# MagMemsAmpli_V6.net
KiCad netlist of a schematic drawn in EAGLE
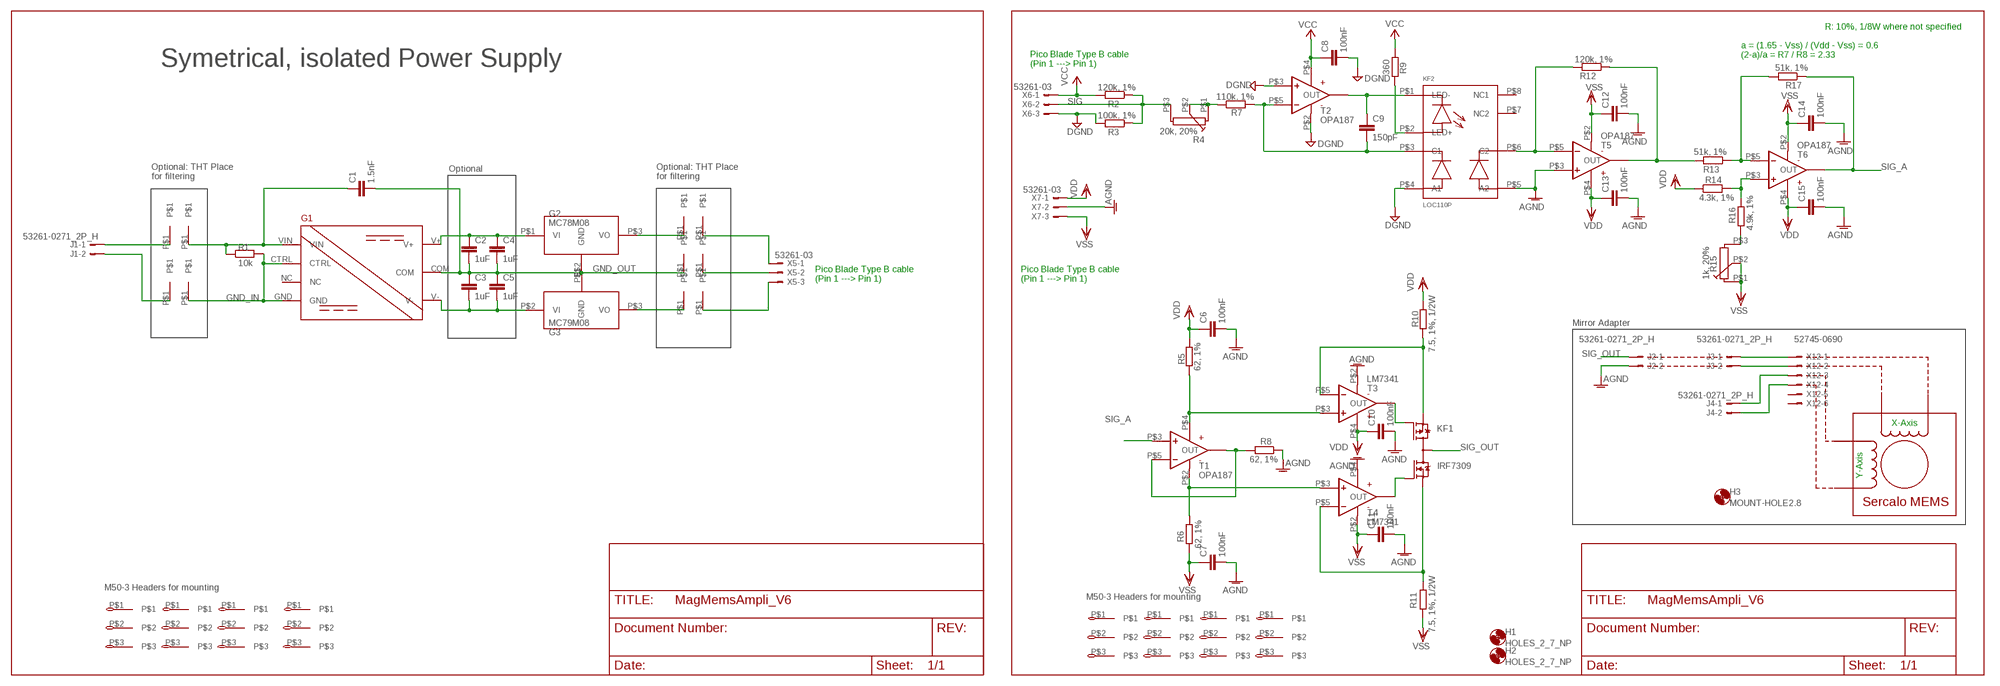
[diagram p0: schematic, sheet 1]

(export (version "E")
  (design (tool "Eeschema 10.0.6"))
  (components
    (comp (ref "C1")
      (value "1.5nF")
      (footprint "eagle-import:C0805K")
      (libsource (lib "eagle-import") (part "C-EUC0805K"))
    )
    (comp (ref "C2")
      (value "1uF")
      (footprint "eagle-import:C0805K")
      (libsource (lib "eagle-import") (part "C-EUC0805K"))
    )
    (comp (ref "C3")
      (value "1uF")
      (footprint "eagle-import:C0805K")
      (libsource (lib "eagle-import") (part "C-EUC0805K"))
    )
    (comp (ref "C4")
      (value "1uF")
      (footprint "eagle-import:C0805K")
      (libsource (lib "eagle-import") (part "C-EUC0805K"))
    )
    (comp (ref "C5")
      (value "1uF")
      (footprint "eagle-import:C0805K")
      (libsource (lib "eagle-import") (part "C-EUC0805K"))
    )
    (comp (ref "C6")
      (value "100nF")
      (footprint "eagle-import:C0603K")
      (libsource (lib "eagle-import") (part "C-EUC0603K"))
    )
    (comp (ref "C7")
      (value "100nF")
      (footprint "eagle-import:C0603K")
      (libsource (lib "eagle-import") (part "C-EUC0603K"))
    )
    (comp (ref "C8")
      (value "100nF")
      (footprint "eagle-import:C0603K")
      (libsource (lib "eagle-import") (part "C-EUC0603K"))
    )
    (comp (ref "C9")
      (value "150pF")
      (footprint "eagle-import:C0603K")
      (libsource (lib "eagle-import") (part "C-EUC0603K"))
    )
    (comp (ref "C10")
      (value "100nF")
      (footprint "eagle-import:C0603K")
      (libsource (lib "eagle-import") (part "C-EUC0603K"))
    )
    (comp (ref "C11")
      (value "100nF")
      (footprint "eagle-import:C0603K")
      (libsource (lib "eagle-import") (part "C-EUC0603K"))
    )
    (comp (ref "C12")
      (value "100nF")
      (footprint "eagle-import:C0603K")
      (libsource (lib "eagle-import") (part "C-EUC0603K"))
    )
    (comp (ref "C13")
      (value "100nF")
      (footprint "eagle-import:C0603K")
      (libsource (lib "eagle-import") (part "C-EUC0603K"))
    )
    (comp (ref "C14")
      (value "100nF")
      (footprint "eagle-import:C0603K")
      (libsource (lib "eagle-import") (part "C-EUC0603K"))
    )
    (comp (ref "C15")
      (value "100nF")
      (footprint "eagle-import:C0603K")
      (libsource (lib "eagle-import") (part "C-EUC0603K"))
    )
    (comp (ref "G1")
      (value "RS6-0512D")
      (footprint "eagle-import:RS_THT")
      (fields (field (name "MANUFACTURER") "Recom Power"))
      (libsource (lib "eagle-import") (part "RS6-0512D"))
    )
    (comp (ref "G2")
      (value "MC78M08")
      (footprint "eagle-import:DPAK-3")
      (fields (field (name "MOUSER") "MC78M08CDTG"))
      (libsource (lib "eagle-import") (part "MC78M08"))
    )
    (comp (ref "G3")
      (value "MC79M08")
      (footprint "eagle-import:DPAK-3")
      (libsource (lib "eagle-import") (part "MC79M08"))
    )
    (comp (ref "H1")
      (value "HOLES_2_7_NP")
      (footprint "eagle-import:2_7_NP")
      (libsource (lib "eagle-import") (part "HOLES_2_7_NP"))
    )
    (comp (ref "H2")
      (value "HOLES_2_7_NP")
      (footprint "eagle-import:2_7_NP")
      (libsource (lib "eagle-import") (part "HOLES_2_7_NP"))
    )
    (comp (ref "H3")
      (value "MOUNT-HOLE2.8")
      (footprint "eagle-import:2,8")
      (libsource (lib "eagle-import") (part "MOUNT-HOLE2.8"))
    )
    (comp (ref "J1")
      (value "53261-0271_2P_H")
      (footprint "eagle-import:53261-02")
      (fields (field (name "MANUFACTURER") "Molex") (field (name "PREIS") "0.84"))
      (libsource (lib "eagle-import") (part "53261-0271_2P_H"))
    )
    (comp (ref "J2")
      (value "53261-0271_2P_H")
      (footprint "eagle-import:53261-02")
      (fields (field (name "MANUFACTURER") "Molex") (field (name "PREIS") "0.84"))
      (libsource (lib "eagle-import") (part "53261-0271_2P_H"))
    )
    (comp (ref "J3")
      (value "53261-0271_2P_H")
      (footprint "eagle-import:53261-02")
      (fields (field (name "MANUFACTURER") "Molex") (field (name "PREIS") "0.84"))
      (libsource (lib "eagle-import") (part "53261-0271_2P_H"))
    )
    (comp (ref "J4")
      (value "53261-0271_2P_H")
      (footprint "eagle-import:53261-02")
      (fields (field (name "MANUFACTURER") "Molex") (field (name "PREIS") "0.84"))
      (libsource (lib "eagle-import") (part "53261-0271_2P_H"))
    )
    (comp (ref "KF1")
      (value "IRF7309")
      (footprint "eagle-import:SO08-IRF")
      (libsource (lib "eagle-import") (part "IRF7309"))
    )
    (comp (ref "KF2")
      (value "LOC110P")
      (footprint "eagle-import:LOC110P")
      (libsource (lib "eagle-import") (part "LOC110P"))
    )
    (comp (ref "R1")
      (value "10k")
      (footprint "eagle-import:R0603")
      (libsource (lib "eagle-import") (part "R-EU_R0603"))
    )
    (comp (ref "R2")
      (value "120k, 1%")
      (footprint "eagle-import:R0603")
      (libsource (lib "eagle-import") (part "R-EU_R0603"))
    )
    (comp (ref "R3")
      (value "100k, 1%")
      (footprint "eagle-import:R0603")
      (libsource (lib "eagle-import") (part "R-EU_R0603"))
    )
    (comp (ref "R4")
      (value "20k, 20%")
      (footprint "eagle-import:SM-3T")
      (libsource (lib "eagle-import") (part "SM-3T"))
    )
    (comp (ref "R5")
      (value "62, 1%")
      (footprint "eagle-import:R0603")
      (libsource (lib "eagle-import") (part "R-EU_R0603"))
    )
    (comp (ref "R6")
      (value "62, 1%")
      (footprint "eagle-import:R0603")
      (libsource (lib "eagle-import") (part "R-EU_R0603"))
    )
    (comp (ref "R7")
      (value "110k, 1%")
      (footprint "eagle-import:R0603")
      (libsource (lib "eagle-import") (part "R-EU_R0603"))
    )
    (comp (ref "R8")
      (value "62, 1%")
      (footprint "eagle-import:R0603")
      (libsource (lib "eagle-import") (part "R-EU_R0603"))
    )
    (comp (ref "R9")
      (value "360")
      (footprint "eagle-import:R0603")
      (libsource (lib "eagle-import") (part "R-EU_R0603"))
    )
    (comp (ref "R10")
      (value "7.5, 1%, 1/2W")
      (footprint "eagle-import:R0805")
      (libsource (lib "eagle-import") (part "R-EU_R0805"))
    )
    (comp (ref "R11")
      (value "7.5, 1%, 1/2W")
      (footprint "eagle-import:R0805")
      (libsource (lib "eagle-import") (part "R-EU_R0805"))
    )
    (comp (ref "R12")
      (value "120k, 1%")
      (footprint "eagle-import:R0603")
      (libsource (lib "eagle-import") (part "R-EU_R0603"))
    )
    (comp (ref "R13")
      (value "51k, 1%")
      (footprint "eagle-import:R0603")
      (libsource (lib "eagle-import") (part "R-EU_R0603"))
    )
    (comp (ref "R14")
      (value "4.3k, 1%")
      (footprint "eagle-import:R0603")
      (libsource (lib "eagle-import") (part "R-EU_R0603"))
    )
    (comp (ref "R15")
      (value "1k, 20%")
      (footprint "eagle-import:SM-3T")
      (libsource (lib "eagle-import") (part "SM-3T"))
    )
    (comp (ref "R16")
      (value "4.9k, 1%")
      (footprint "eagle-import:R0603")
      (libsource (lib "eagle-import") (part "R-EU_R0603"))
    )
    (comp (ref "R17")
      (value "51k, 1%")
      (footprint "eagle-import:R0603")
      (libsource (lib "eagle-import") (part "R-EU_R0603"))
    )
    (comp (ref "T1")
      (value "OPA187")
      (footprint "eagle-import:SOT23-5")
      (libsource (lib "eagle-import") (part "OPA187"))
    )
    (comp (ref "T2")
      (value "OPA187")
      (footprint "eagle-import:SOT23-5")
      (libsource (lib "eagle-import") (part "OPA187"))
    )
    (comp (ref "T3")
      (value "LM7341")
      (footprint "eagle-import:SOT23-5")
      (libsource (lib "eagle-import") (part "LM7341"))
    )
    (comp (ref "T4")
      (value "LM7341")
      (footprint "eagle-import:SOT23-5")
      (libsource (lib "eagle-import") (part "LM7341"))
    )
    (comp (ref "T5")
      (value "OPA187")
      (footprint "eagle-import:SOT23-5")
      (libsource (lib "eagle-import") (part "OPA187"))
    )
    (comp (ref "T6")
      (value "OPA187")
      (footprint "eagle-import:SOT23-5")
      (libsource (lib "eagle-import") (part "OPA187"))
    )
    (comp (ref "TP1")
      (value "TP10")
      (footprint "eagle-import:TP10")
      (libsource (lib "eagle-import") (part "TP10"))
    )
    (comp (ref "TP2")
      (value "TP10")
      (footprint "eagle-import:TP10")
      (libsource (lib "eagle-import") (part "TP10"))
    )
    (comp (ref "TP3")
      (value "TP10")
      (footprint "eagle-import:TP10")
      (libsource (lib "eagle-import") (part "TP10"))
    )
    (comp (ref "TP4")
      (value "TP10")
      (footprint "eagle-import:TP10")
      (libsource (lib "eagle-import") (part "TP10"))
    )
    (comp (ref "TP5")
      (value "TP10")
      (footprint "eagle-import:TP10")
      (libsource (lib "eagle-import") (part "TP10"))
    )
    (comp (ref "TP6")
      (value "TP10")
      (footprint "eagle-import:TP10")
      (libsource (lib "eagle-import") (part "TP10"))
    )
    (comp (ref "TP7")
      (value "TP10")
      (footprint "eagle-import:TP10")
      (libsource (lib "eagle-import") (part "TP10"))
    )
    (comp (ref "TP8")
      (value "TP10")
      (footprint "eagle-import:TP10")
      (libsource (lib "eagle-import") (part "TP10"))
    )
    (comp (ref "TP9")
      (value "TP10")
      (footprint "eagle-import:TP10")
      (libsource (lib "eagle-import") (part "TP10"))
    )
    (comp (ref "TP10")
      (value "TP10")
      (footprint "eagle-import:TP10")
      (libsource (lib "eagle-import") (part "TP10"))
    )
    (comp (ref "X1")
      (value "M50-3")
      (footprint "eagle-import:M50-3")
      (libsource (lib "eagle-import") (part "M50-3"))
    )
    (comp (ref "X2")
      (value "M50-3")
      (footprint "eagle-import:M50-3")
      (libsource (lib "eagle-import") (part "M50-3"))
    )
    (comp (ref "X3")
      (value "M50-3")
      (footprint "eagle-import:M50-3")
      (libsource (lib "eagle-import") (part "M50-3"))
    )
    (comp (ref "X4")
      (value "M50-3")
      (footprint "eagle-import:M50-3")
      (libsource (lib "eagle-import") (part "M50-3"))
    )
    (comp (ref "X5")
      (value "53261-03")
      (footprint "eagle-import:53261-03")
      (fields
        (field (name "MF") "MOLEX")
        (field (name "MPN") "53261-0390")
        (field (name "MOUSER") "53261-0371 ")
        (field (name "PREIS") "0.52")
      )
      (libsource (lib "eagle-import") (part "53?-03261"))
    )
    (comp (ref "X6")
      (value "53261-03")
      (footprint "eagle-import:53261-03")
      (fields
        (field (name "MF") "MOLEX")
        (field (name "MPN") "53261-0390")
        (field (name "MOUSER") "53261-0371 ")
        (field (name "PREIS") "0.52")
      )
      (libsource (lib "eagle-import") (part "53?-03261"))
    )
    (comp (ref "X7")
      (value "53261-03")
      (footprint "eagle-import:53261-03")
      (fields
        (field (name "MF") "MOLEX")
        (field (name "MPN") "53261-0390")
        (field (name "MOUSER") "53261-0371")
        (field (name "PREIS") "0.52")
      )
      (libsource (lib "eagle-import") (part "53?-03261"))
    )
    (comp (ref "X8")
      (value "M50-3")
      (footprint "eagle-import:M50-3")
      (libsource (lib "eagle-import") (part "M50-3"))
    )
    (comp (ref "X9")
      (value "M50-3")
      (footprint "eagle-import:M50-3")
      (libsource (lib "eagle-import") (part "M50-3"))
    )
    (comp (ref "X10")
      (value "M50-3")
      (footprint "eagle-import:M50-3")
      (libsource (lib "eagle-import") (part "M50-3"))
    )
    (comp (ref "X11")
      (value "M50-3")
      (footprint "eagle-import:M50-3")
      (libsource (lib "eagle-import") (part "M50-3"))
    )
    (comp (ref "X12")
      (value "52745-0690")
      (footprint "eagle-import:52745-0690")
      (fields (field (name "MF") "MOLEX") (field (name "MOUSER") "52745-0697") (field (name "PREIS") "0.796"))
      (libsource (lib "eagle-import") (part "52745-0690"))
    )
  )
  (nets
    (net (code "1") (name "/GND_IN") (class "Default")
      (node (ref "G1") (pin "CTRL") (pinfunction "CTRL_CTRL") (pintype "bidirectional"))
      (node (ref "G1") (pin "GND") (pinfunction "GND_GND") (pintype "bidirectional"))
      (node (ref "R1") (pin "2") (pinfunction "2_2") (pintype "passive"))
      (node (ref "TP4") (pin "P$1") (pinfunction "P$1_P$1") (pintype "bidirectional"))
    )
    (net (code "2") (name "/GND_OUT") (class "Default")
      (node (ref "C1") (pin "2") (pinfunction "2_2") (pintype "passive"))
      (node (ref "C2") (pin "2") (pinfunction "2_2") (pintype "passive"))
      (node (ref "C3") (pin "1") (pinfunction "1_1") (pintype "passive"))
      (node (ref "C4") (pin "2") (pinfunction "2_2") (pintype "passive"))
      (node (ref "C5") (pin "1") (pinfunction "1_1") (pintype "passive"))
      (node (ref "G1") (pin "COM") (pinfunction "COM_COM") (pintype "bidirectional"))
      (node (ref "G2") (pin "P$2") (pinfunction "GND_P$2") (pintype "bidirectional"))
      (node (ref "G3") (pin "P$1") (pinfunction "GND_P$1") (pintype "bidirectional"))
      (node (ref "TP6") (pin "P$1") (pinfunction "P$1_P$1") (pintype "bidirectional"))
    )
    (net (code "3") (name "/SIG") (class "Default")
      (node (ref "R2") (pin "1") (pinfunction "1_1") (pintype "passive"))
      (node (ref "R3") (pin "1") (pinfunction "1_1") (pintype "passive"))
      (node (ref "R4") (pin "P$3") (pinfunction "1E_P$3") (pintype "passive"))
      (node (ref "X6") (pin "2") (pinfunction "S_2") (pintype "passive"))
    )
    (net (code "4") (name "/SIG_A") (class "Default")
      (node (ref "R17") (pin "1") (pinfunction "1_1") (pintype "passive"))
      (node (ref "T1") (pin "P$3") (pinfunction "+IN_P$3") (pintype "input"))
      (node (ref "T6") (pin "P$1") (pinfunction "OUT_P$1") (pintype "bidirectional"))
    )
    (net (code "5") (name "/SIG_OUT") (class "Default")
      (node (ref "J2") (pin "1") (pinfunction "S_1") (pintype "passive"))
      (node (ref "KF1") (pin "5") (pinfunction "D_5") (pintype "passive"))
      (node (ref "KF1") (pin "6") (pinfunction "D_6") (pintype "passive"))
      (node (ref "KF1") (pin "7") (pinfunction "D_7") (pintype "passive"))
      (node (ref "KF1") (pin "8") (pinfunction "D_8") (pintype "passive"))
    )
    (net (code "6") (name "AGND") (class "Default")
      (node (ref "C10") (pin "2") (pinfunction "2_2") (pintype "passive"))
      (node (ref "C11") (pin "2") (pinfunction "2_2") (pintype "passive"))
      (node (ref "C12") (pin "2") (pinfunction "2_2") (pintype "passive"))
      (node (ref "C13") (pin "2") (pinfunction "2_2") (pintype "passive"))
      (node (ref "C14") (pin "2") (pinfunction "2_2") (pintype "passive"))
      (node (ref "C15") (pin "2") (pinfunction "2_2") (pintype "passive"))
      (node (ref "C6") (pin "2") (pinfunction "2_2") (pintype "passive"))
      (node (ref "C7") (pin "2") (pinfunction "2_2") (pintype "passive"))
      (node (ref "J2") (pin "2") (pinfunction "S_2") (pintype "passive"))
      (node (ref "KF2") (pin "P$5") (pinfunction "A2_P$5") (pintype "bidirectional"))
      (node (ref "R8") (pin "1") (pinfunction "1_1") (pintype "passive"))
      (node (ref "T3") (pin "P$2") (pinfunction "V-_P$2") (pintype "passive"))
      (node (ref "T4") (pin "P$4") (pinfunction "V+_P$4") (pintype "passive"))
      (node (ref "T5") (pin "P$3") (pinfunction "+IN_P$3") (pintype "input"))
      (node (ref "X7") (pin "2") (pinfunction "S_2") (pintype "passive"))
    )
    (net (code "7") (name "DGND") (class "Default")
      (node (ref "C8") (pin "2") (pinfunction "2_2") (pintype "passive"))
      (node (ref "KF2") (pin "P$4") (pinfunction "A1_P$4") (pintype "bidirectional"))
      (node (ref "R3") (pin "2") (pinfunction "2_2") (pintype "passive"))
      (node (ref "T2") (pin "P$2") (pinfunction "V-_P$2") (pintype "passive"))
      (node (ref "T2") (pin "P$3") (pinfunction "+IN_P$3") (pintype "input"))
      (node (ref "X6") (pin "3") (pinfunction "S_3") (pintype "passive"))
    )
    (net (code "8") (name "Net-(C1-Pad1)") (class "Default")
      (node (ref "C1") (pin "1") (pinfunction "1_1") (pintype "passive"))
      (node (ref "G1") (pin "VIN") (pinfunction "VIN_VIN") (pintype "bidirectional"))
      (node (ref "R1") (pin "1") (pinfunction "1_1") (pintype "passive"))
      (node (ref "TP3") (pin "P$1") (pinfunction "P$1_P$1") (pintype "bidirectional"))
    )
    (net (code "9") (name "Net-(G2-VI)") (class "Default")
      (node (ref "C2") (pin "1") (pinfunction "1_1") (pintype "passive"))
      (node (ref "C4") (pin "1") (pinfunction "1_1") (pintype "passive"))
      (node (ref "G1") (pin "V+") (pinfunction "V+_V+") (pintype "bidirectional"))
      (node (ref "G2") (pin "P$1") (pinfunction "VI_P$1") (pintype "bidirectional"))
    )
    (net (code "10") (name "Net-(G2-VO)") (class "Default")
      (node (ref "G2") (pin "P$3") (pinfunction "VO_P$3") (pintype "bidirectional"))
      (node (ref "TP5") (pin "P$1") (pinfunction "P$1_P$1") (pintype "bidirectional"))
    )
    (net (code "11") (name "Net-(G3-VI)") (class "Default")
      (node (ref "C3") (pin "2") (pinfunction "2_2") (pintype "passive"))
      (node (ref "C5") (pin "2") (pinfunction "2_2") (pintype "passive"))
      (node (ref "G1") (pin "V-") (pinfunction "V-_V-") (pintype "bidirectional"))
      (node (ref "G3") (pin "P$2") (pinfunction "VI_P$2") (pintype "bidirectional"))
    )
    (net (code "12") (name "Net-(G3-VO)") (class "Default")
      (node (ref "G3") (pin "P$3") (pinfunction "VO_P$3") (pintype "bidirectional"))
      (node (ref "TP7") (pin "P$1") (pinfunction "P$1_P$1") (pintype "bidirectional"))
    )
    (net (code "13") (name "Net-(J1A-S)") (class "Default")
      (node (ref "J1") (pin "1") (pinfunction "S_1") (pintype "passive"))
      (node (ref "TP1") (pin "P$1") (pinfunction "P$1_P$1") (pintype "bidirectional"))
    )
    (net (code "14") (name "Net-(J1B-S)") (class "Default")
      (node (ref "J1") (pin "2") (pinfunction "S_2") (pintype "passive"))
      (node (ref "TP2") (pin "P$1") (pinfunction "P$1_P$1") (pintype "bidirectional"))
    )
    (net (code "15") (name "Net-(J3A-S)") (class "Default")
      (node (ref "J3") (pin "1") (pinfunction "S_1") (pintype "passive"))
      (node (ref "X12") (pin "1") (pinfunction "S_1") (pintype "passive"))
    )
    (net (code "16") (name "Net-(J3B-S)") (class "Default")
      (node (ref "J3") (pin "2") (pinfunction "S_2") (pintype "passive"))
      (node (ref "X12") (pin "2") (pinfunction "S_2") (pintype "passive"))
    )
    (net (code "17") (name "Net-(J4A-S)") (class "Default")
      (node (ref "J4") (pin "1") (pinfunction "S_1") (pintype "passive"))
      (node (ref "X12") (pin "3") (pinfunction "S_3") (pintype "passive"))
    )
    (net (code "18") (name "Net-(J4B-S)") (class "Default")
      (node (ref "J4") (pin "2") (pinfunction "S_2") (pintype "passive"))
      (node (ref "X12") (pin "4") (pinfunction "S_4") (pintype "passive"))
    )
    (net (code "19") (name "Net-(KF1-N-G)") (class "Default")
      (node (ref "KF1") (pin "2") (pinfunction "N-G_2") (pintype "passive"))
      (node (ref "T4") (pin "P$1") (pinfunction "OUT_P$1") (pintype "bidirectional"))
    )
    (net (code "20") (name "Net-(KF1-N-S)") (class "Default")
      (node (ref "KF1") (pin "1") (pinfunction "N-S_1") (pintype "passive"))
      (node (ref "R11") (pin "2") (pinfunction "2_2") (pintype "passive"))
      (node (ref "T4") (pin "P$5") (pinfunction "-IN_P$5") (pintype "input"))
    )
    (net (code "21") (name "Net-(KF1-P-G)") (class "Default")
      (node (ref "KF1") (pin "4") (pinfunction "P-G_4") (pintype "passive"))
      (node (ref "T3") (pin "P$1") (pinfunction "OUT_P$1") (pintype "bidirectional"))
    )
    (net (code "22") (name "Net-(KF1-P-S)") (class "Default")
      (node (ref "KF1") (pin "3") (pinfunction "P-S_3") (pintype "passive"))
      (node (ref "R10") (pin "1") (pinfunction "1_1") (pintype "passive"))
      (node (ref "T3") (pin "P$5") (pinfunction "-IN_P$5") (pintype "input"))
    )
    (net (code "23") (name "Net-(KF2-C1)") (class "Default")
      (node (ref "C9") (pin "2") (pinfunction "2_2") (pintype "passive"))
      (node (ref "KF2") (pin "P$3") (pinfunction "C1_P$3") (pintype "bidirectional"))
      (node (ref "R7") (pin "2") (pinfunction "2_2") (pintype "passive"))
      (node (ref "T2") (pin "P$5") (pinfunction "-IN_P$5") (pintype "input"))
    )
    (net (code "24") (name "Net-(KF2-C2)") (class "Default")
      (node (ref "KF2") (pin "P$6") (pinfunction "C2_P$6") (pintype "bidirectional"))
      (node (ref "R12") (pin "2") (pinfunction "2_2") (pintype "passive"))
      (node (ref "T5") (pin "P$5") (pinfunction "-IN_P$5") (pintype "input"))
    )
    (net (code "25") (name "Net-(KF2-LED+)") (class "Default")
      (node (ref "KF2") (pin "P$2") (pinfunction "LED+_P$2") (pintype "bidirectional"))
      (node (ref "R9") (pin "1") (pinfunction "1_1") (pintype "passive"))
    )
    (net (code "26") (name "Net-(KF2-LED-)") (class "Default")
      (node (ref "C9") (pin "1") (pinfunction "1_1") (pintype "passive"))
      (node (ref "KF2") (pin "P$1") (pinfunction "LED-_P$1") (pintype "bidirectional"))
      (node (ref "T2") (pin "P$1") (pinfunction "OUT_P$1") (pintype "bidirectional"))
    )
    (net (code "27") (name "Net-(R4-1A)") (class "Default")
      (node (ref "R4") (pin "P$1") (pinfunction "1A_P$1") (pintype "passive"))
      (node (ref "R4") (pin "P$2") (pinfunction "1S_P$2") (pintype "passive"))
      (node (ref "R7") (pin "1") (pinfunction "1_1") (pintype "passive"))
    )
    (net (code "28") (name "Net-(R15-1E)") (class "Default")
      (node (ref "R15") (pin "P$3") (pinfunction "1E_P$3") (pintype "passive"))
      (node (ref "R16") (pin "1") (pinfunction "1_1") (pintype "passive"))
    )
    (net (code "29") (name "Net-(T1--IN)") (class "Default")
      (node (ref "R8") (pin "2") (pinfunction "2_2") (pintype "passive"))
      (node (ref "T1") (pin "P$1") (pinfunction "OUT_P$1") (pintype "bidirectional"))
      (node (ref "T1") (pin "P$5") (pinfunction "-IN_P$5") (pintype "input"))
    )
    (net (code "30") (name "Net-(T1-V+)") (class "Default")
      (node (ref "R5") (pin "1") (pinfunction "1_1") (pintype "passive"))
      (node (ref "T1") (pin "P$4") (pinfunction "V+_P$4") (pintype "passive"))
      (node (ref "T3") (pin "P$3") (pinfunction "+IN_P$3") (pintype "input"))
    )
    (net (code "31") (name "Net-(T1-V-)") (class "Default")
      (node (ref "R6") (pin "2") (pinfunction "2_2") (pintype "passive"))
      (node (ref "T1") (pin "P$2") (pinfunction "V-_P$2") (pintype "passive"))
      (node (ref "T4") (pin "P$3") (pinfunction "+IN_P$3") (pintype "input"))
    )
    (net (code "32") (name "Net-(T5-OUT)") (class "Default")
      (node (ref "R12") (pin "1") (pinfunction "1_1") (pintype "passive"))
      (node (ref "R13") (pin "2") (pinfunction "2_2") (pintype "passive"))
      (node (ref "T5") (pin "P$1") (pinfunction "OUT_P$1") (pintype "bidirectional"))
    )
    (net (code "33") (name "Net-(T6-+IN)") (class "Default")
      (node (ref "R14") (pin "2") (pinfunction "2_2") (pintype "passive"))
      (node (ref "R16") (pin "2") (pinfunction "2_2") (pintype "passive"))
      (node (ref "T6") (pin "P$3") (pinfunction "+IN_P$3") (pintype "input"))
    )
    (net (code "34") (name "Net-(T6--IN)") (class "Default")
      (node (ref "R13") (pin "1") (pinfunction "1_1") (pintype "passive"))
      (node (ref "R17") (pin "2") (pinfunction "2_2") (pintype "passive"))
      (node (ref "T6") (pin "P$5") (pinfunction "-IN_P$5") (pintype "input"))
    )
    (net (code "35") (name "Net-(X5A-S)") (class "Default")
      (node (ref "TP8") (pin "P$1") (pinfunction "P$1_P$1") (pintype "bidirectional"))
      (node (ref "X5") (pin "1") (pinfunction "S_1") (pintype "passive"))
    )
    (net (code "36") (name "Net-(X5B-S)") (class "Default")
      (node (ref "TP9") (pin "P$1") (pinfunction "P$1_P$1") (pintype "bidirectional"))
      (node (ref "X5") (pin "2") (pinfunction "S_2") (pintype "passive"))
    )
    (net (code "37") (name "Net-(X5C-S)") (class "Default")
      (node (ref "TP10") (pin "P$1") (pinfunction "P$1_P$1") (pintype "bidirectional"))
      (node (ref "X5") (pin "3") (pinfunction "S_3") (pintype "passive"))
    )
    (net (code "38") (name "VCC") (class "Default")
      (node (ref "C8") (pin "1") (pinfunction "1_1") (pintype "passive"))
      (node (ref "R2") (pin "2") (pinfunction "2_2") (pintype "passive"))
      (node (ref "R9") (pin "2") (pinfunction "2_2") (pintype "passive"))
      (node (ref "T2") (pin "P$4") (pinfunction "V+_P$4") (pintype "passive"))
      (node (ref "X6") (pin "1") (pinfunction "S_1") (pintype "passive"))
    )
    (net (code "39") (name "VDD") (class "Default")
      (node (ref "C10") (pin "1") (pinfunction "1_1") (pintype "passive"))
      (node (ref "C13") (pin "1") (pinfunction "1_1") (pintype "passive"))
      (node (ref "C15") (pin "1") (pinfunction "1_1") (pintype "passive"))
      (node (ref "C6") (pin "1") (pinfunction "1_1") (pintype "passive"))
      (node (ref "R10") (pin "2") (pinfunction "2_2") (pintype "passive"))
      (node (ref "R14") (pin "1") (pinfunction "1_1") (pintype "passive"))
      (node (ref "R5") (pin "2") (pinfunction "2_2") (pintype "passive"))
      (node (ref "T3") (pin "P$4") (pinfunction "V+_P$4") (pintype "passive"))
      (node (ref "T5") (pin "P$4") (pinfunction "V+_P$4") (pintype "passive"))
      (node (ref "T6") (pin "P$4") (pinfunction "V+_P$4") (pintype "passive"))
      (node (ref "X7") (pin "1") (pinfunction "S_1") (pintype "passive"))
    )
    (net (code "40") (name "VSS") (class "Default")
      (node (ref "C11") (pin "1") (pinfunction "1_1") (pintype "passive"))
      (node (ref "C12") (pin "1") (pinfunction "1_1") (pintype "passive"))
      (node (ref "C14") (pin "1") (pinfunction "1_1") (pintype "passive"))
      (node (ref "C7") (pin "1") (pinfunction "1_1") (pintype "passive"))
      (node (ref "R11") (pin "1") (pinfunction "1_1") (pintype "passive"))
      (node (ref "R15") (pin "P$1") (pinfunction "1A_P$1") (pintype "passive"))
      (node (ref "R15") (pin "P$2") (pinfunction "1S_P$2") (pintype "passive"))
      (node (ref "R6") (pin "1") (pinfunction "1_1") (pintype "passive"))
      (node (ref "T4") (pin "P$2") (pinfunction "V-_P$2") (pintype "passive"))
      (node (ref "T5") (pin "P$2") (pinfunction "V-_P$2") (pintype "passive"))
      (node (ref "T6") (pin "P$2") (pinfunction "V-_P$2") (pintype "passive"))
      (node (ref "X7") (pin "3") (pinfunction "S_3") (pintype "passive"))
    )
    (net (code "41") (name "unconnected-(G1-PadNC)") (class "Default")
      (node (ref "G1") (pin "NC") (pinfunction "NC_NC") (pintype "bidirectional"))
    )
    (net (code "42") (name "unconnected-(KF2-NC1-PadP$8)") (class "Default")
      (node (ref "KF2") (pin "P$8") (pinfunction "NC1_P$8") (pintype "bidirectional"))
    )
    (net (code "43") (name "unconnected-(KF2-NC2-PadP$7)") (class "Default")
      (node (ref "KF2") (pin "P$7") (pinfunction "NC2_P$7") (pintype "bidirectional"))
    )
    (net (code "44") (name "unconnected-(X1-PadP$1)") (class "Default")
      (node (ref "X1") (pin "P$1") (pinfunction "P$1_P$1") (pintype "bidirectional"))
    )
    (net (code "45") (name "unconnected-(X1-PadP$2)") (class "Default")
      (node (ref "X1") (pin "P$2") (pinfunction "P$2_P$2") (pintype "bidirectional"))
    )
    (net (code "46") (name "unconnected-(X1-PadP$3)") (class "Default")
      (node (ref "X1") (pin "P$3") (pinfunction "P$3_P$3") (pintype "bidirectional"))
    )
    (net (code "47") (name "unconnected-(X2-PadP$1)") (class "Default")
      (node (ref "X2") (pin "P$1") (pinfunction "P$1_P$1") (pintype "bidirectional"))
    )
    (net (code "48") (name "unconnected-(X2-PadP$2)") (class "Default")
      (node (ref "X2") (pin "P$2") (pinfunction "P$2_P$2") (pintype "bidirectional"))
    )
    (net (code "49") (name "unconnected-(X2-PadP$3)") (class "Default")
      (node (ref "X2") (pin "P$3") (pinfunction "P$3_P$3") (pintype "bidirectional"))
    )
    (net (code "50") (name "unconnected-(X3-PadP$1)") (class "Default")
      (node (ref "X3") (pin "P$1") (pinfunction "P$1_P$1") (pintype "bidirectional"))
    )
    (net (code "51") (name "unconnected-(X3-PadP$2)") (class "Default")
      (node (ref "X3") (pin "P$2") (pinfunction "P$2_P$2") (pintype "bidirectional"))
    )
    (net (code "52") (name "unconnected-(X3-PadP$3)") (class "Default")
      (node (ref "X3") (pin "P$3") (pinfunction "P$3_P$3") (pintype "bidirectional"))
    )
    (net (code "53") (name "unconnected-(X4-PadP$1)") (class "Default")
      (node (ref "X4") (pin "P$1") (pinfunction "P$1_P$1") (pintype "bidirectional"))
    )
    (net (code "54") (name "unconnected-(X4-PadP$2)") (class "Default")
      (node (ref "X4") (pin "P$2") (pinfunction "P$2_P$2") (pintype "bidirectional"))
    )
    (net (code "55") (name "unconnected-(X4-PadP$3)") (class "Default")
      (node (ref "X4") (pin "P$3") (pinfunction "P$3_P$3") (pintype "bidirectional"))
    )
    (net (code "56") (name "unconnected-(X8-PadP$1)") (class "Default")
      (node (ref "X8") (pin "P$1") (pinfunction "P$1_P$1") (pintype "bidirectional"))
    )
    (net (code "57") (name "unconnected-(X8-PadP$2)") (class "Default")
      (node (ref "X8") (pin "P$2") (pinfunction "P$2_P$2") (pintype "bidirectional"))
    )
    (net (code "58") (name "unconnected-(X8-PadP$3)") (class "Default")
      (node (ref "X8") (pin "P$3") (pinfunction "P$3_P$3") (pintype "bidirectional"))
    )
    (net (code "59") (name "unconnected-(X9-PadP$1)") (class "Default")
      (node (ref "X9") (pin "P$1") (pinfunction "P$1_P$1") (pintype "bidirectional"))
    )
    (net (code "60") (name "unconnected-(X9-PadP$2)") (class "Default")
      (node (ref "X9") (pin "P$2") (pinfunction "P$2_P$2") (pintype "bidirectional"))
    )
    (net (code "61") (name "unconnected-(X9-PadP$3)") (class "Default")
      (node (ref "X9") (pin "P$3") (pinfunction "P$3_P$3") (pintype "bidirectional"))
    )
    (net (code "62") (name "unconnected-(X10-PadP$1)") (class "Default")
      (node (ref "X10") (pin "P$1") (pinfunction "P$1_P$1") (pintype "bidirectional"))
    )
    (net (code "63") (name "unconnected-(X10-PadP$2)") (class "Default")
      (node (ref "X10") (pin "P$2") (pinfunction "P$2_P$2") (pintype "bidirectional"))
    )
    (net (code "64") (name "unconnected-(X10-PadP$3)") (class "Default")
      (node (ref "X10") (pin "P$3") (pinfunction "P$3_P$3") (pintype "bidirectional"))
    )
    (net (code "65") (name "unconnected-(X11-PadP$1)") (class "Default")
      (node (ref "X11") (pin "P$1") (pinfunction "P$1_P$1") (pintype "bidirectional"))
    )
    (net (code "66") (name "unconnected-(X11-PadP$2)") (class "Default")
      (node (ref "X11") (pin "P$2") (pinfunction "P$2_P$2") (pintype "bidirectional"))
    )
    (net (code "67") (name "unconnected-(X11-PadP$3)") (class "Default")
      (node (ref "X11") (pin "P$3") (pinfunction "P$3_P$3") (pintype "bidirectional"))
    )
    (net (code "68") (name "unconnected-(X12E-S-Pad5)") (class "Default")
      (node (ref "X12") (pin "5") (pinfunction "S_5") (pintype "passive"))
    )
    (net (code "69") (name "unconnected-(X12F-S-Pad6)") (class "Default")
      (node (ref "X12") (pin "6") (pinfunction "S_6") (pintype "passive"))
    )
  )
)
